# Atomizer_medical_V1_4.net
KiCad netlist of a schematic drawn in Altium Designer
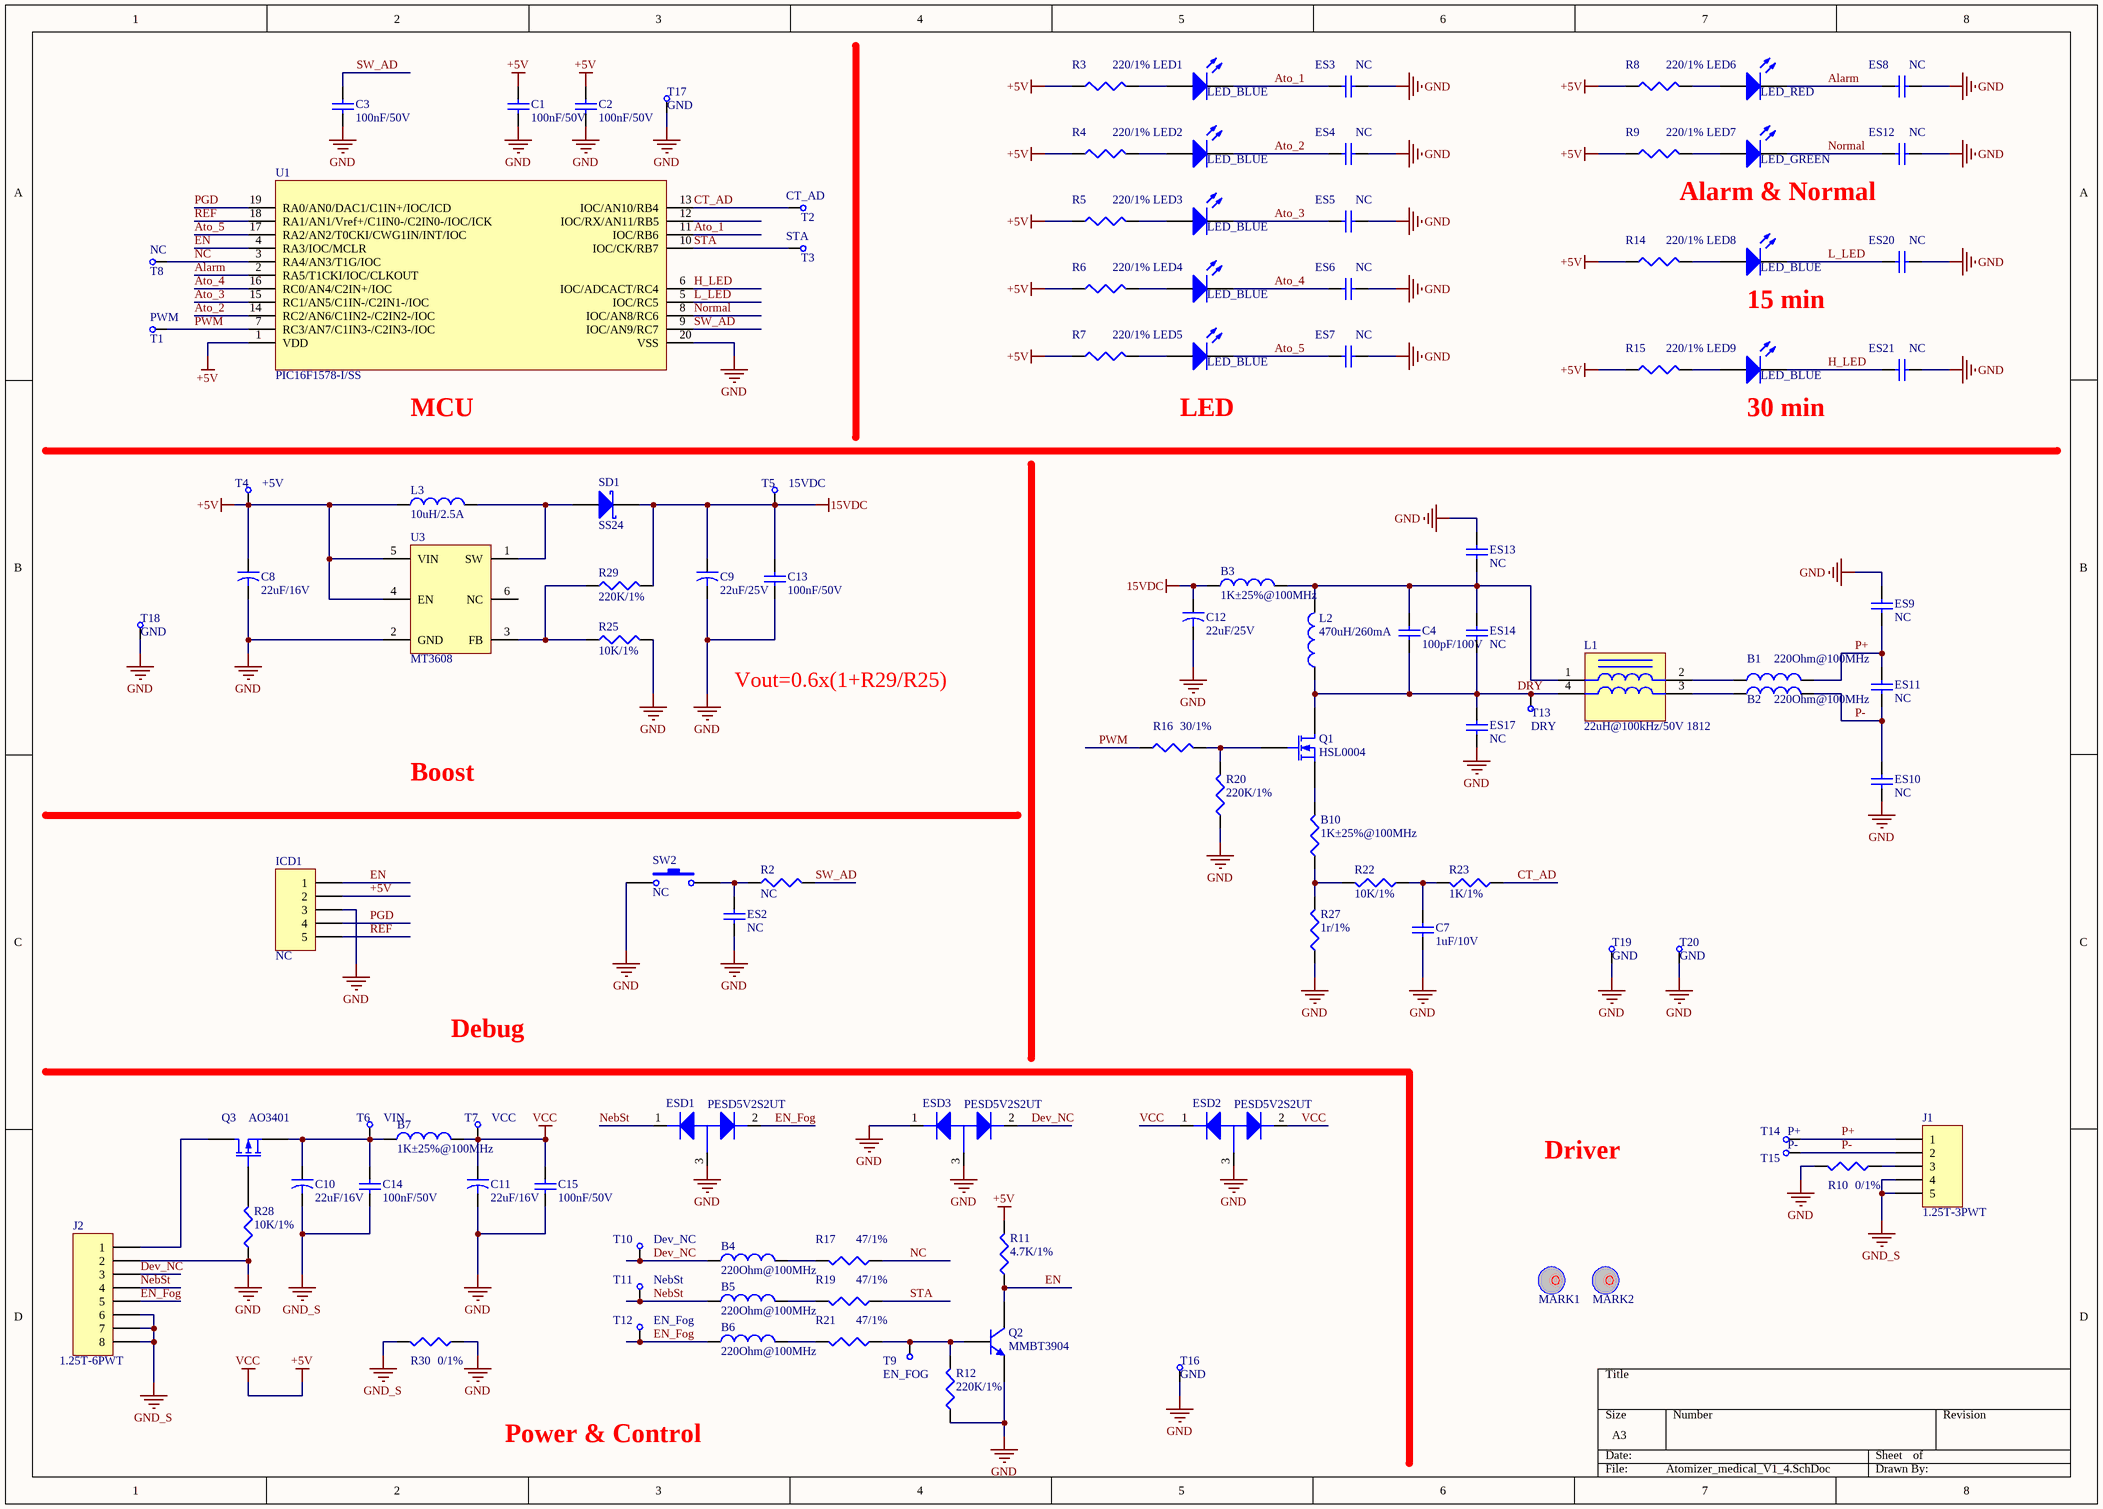
[diagram p0: Atomizer_medical_V1_4.SchDoc]

(export (version "E")
  (design (tool "Eeschema 10.0.6"))
  (components
    (comp (ref "B1")
      (value "220Ohm@100MHz")
      (footprint "0402-B")
      (description "Inductor")
      (fields (field (name "PUBLISHER") "Altium Limited"))
      (libsource (lib "Miscellaneous Devices") (part "Inductor"))
    )
    (comp (ref "B2")
      (value "220Ohm@100MHz")
      (footprint "0402-B")
      (description "Inductor")
      (fields (field (name "PUBLISHER") "Altium Limited"))
      (libsource (lib "Miscellaneous Devices") (part "Inductor"))
    )
    (comp (ref "B3")
      (value "1K±25%@100MHz")
      (footprint "0805-B")
      (description "Inductor")
      (fields (field (name "PUBLISHER") "Altium Limited"))
      (libsource (lib "Miscellaneous Devices") (part "Inductor"))
    )
    (comp (ref "B4")
      (value "220Ohm@100MHz")
      (footprint "0402-B")
      (description "Inductor")
      (fields (field (name "PUBLISHER") "Altium Limited"))
      (libsource (lib "Miscellaneous Devices") (part "Inductor"))
    )
    (comp (ref "B5")
      (value "220Ohm@100MHz")
      (footprint "0402-B")
      (description "Inductor")
      (fields (field (name "PUBLISHER") "Altium Limited"))
      (libsource (lib "Miscellaneous Devices") (part "Inductor"))
    )
    (comp (ref "B6")
      (value "220Ohm@100MHz")
      (footprint "0402-B")
      (description "Inductor")
      (fields (field (name "PUBLISHER") "Altium Limited"))
      (libsource (lib "Miscellaneous Devices") (part "Inductor"))
    )
    (comp (ref "B7")
      (value "1K±25%@100MHz")
      (footprint "0805-B")
      (description "Inductor")
      (fields (field (name "PUBLISHER") "Altium Limited"))
      (libsource (lib "Miscellaneous Devices") (part "Inductor"))
    )
    (comp (ref "B10")
      (value "1K±25%@100MHz")
      (footprint "0603")
      (description "Resistor")
      (fields (field (name "PUBLISHER") "Altium Limited"))
      (libsource (lib "Miscellaneous Devices") (part "Res3"))
    )
    (comp (ref "C1")
      (value "100nF/50V")
      (footprint "0402-C")
      (description "Capacitor (Semiconductor SIM Model)")
      (fields (field (name "PUBLISHER") "Altium Limited"))
      (libsource (lib "Miscellaneous Devices") (part "Cap Semi"))
    )
    (comp (ref "C2")
      (value "100nF/50V")
      (footprint "0402-C")
      (description "Capacitor (Semiconductor SIM Model)")
      (fields (field (name "PUBLISHER") "Altium Limited"))
      (libsource (lib "Miscellaneous Devices") (part "Cap Semi"))
    )
    (comp (ref "C3")
      (value "100nF/50V")
      (footprint "0402-C")
      (description "Capacitor (Semiconductor SIM Model)")
      (fields (field (name "PUBLISHER") "Altium Limited"))
      (libsource (lib "Miscellaneous Devices") (part "Cap Semi"))
    )
    (comp (ref "C4")
      (value "100pF/100V")
      (footprint "0805-C")
      (description "Capacitor (Semiconductor SIM Model)")
      (fields (field (name "PUBLISHER") "Altium Limited"))
      (libsource (lib "Miscellaneous Devices") (part "Cap Semi"))
    )
    (comp (ref "C7")
      (value "1uF/10V")
      (footprint "0402-C")
      (description "Capacitor (Semiconductor SIM Model)")
      (fields (field (name "PUBLISHER") "Altium Limited"))
      (libsource (lib "Miscellaneous Devices") (part "Cap Semi"))
    )
    (comp (ref "C8")
      (value "22uF/16V")
      (footprint "0805-C")
      (description "Capacitor")
      (fields (field (name "PUBLISHER") "Altium Limited"))
      (libsource (lib "Miscellaneous Devices") (part "Cap2"))
    )
    (comp (ref "C9")
      (value "22uF/25V")
      (footprint "1206-C")
      (description "Capacitor")
      (fields (field (name "PUBLISHER") "Altium Limited"))
      (libsource (lib "Miscellaneous Devices") (part "Cap2"))
    )
    (comp (ref "C10")
      (value "22uF/16V")
      (footprint "0805-C")
      (description "Capacitor")
      (fields (field (name "PUBLISHER") "Altium Limited"))
      (libsource (lib "Miscellaneous Devices") (part "Cap2"))
    )
    (comp (ref "C11")
      (value "22uF/16V")
      (footprint "0805-C")
      (description "Capacitor")
      (fields (field (name "PUBLISHER") "Altium Limited"))
      (libsource (lib "Miscellaneous Devices") (part "Cap2"))
    )
    (comp (ref "C12")
      (value "22uF/25V")
      (footprint "1206-C")
      (description "Capacitor")
      (fields (field (name "PUBLISHER") "Altium Limited"))
      (libsource (lib "Miscellaneous Devices") (part "Cap2"))
    )
    (comp (ref "C13")
      (value "100nF/50V")
      (footprint "0402-C")
      (description "Capacitor (Semiconductor SIM Model)")
      (fields (field (name "PUBLISHER") "Altium Limited"))
      (libsource (lib "Miscellaneous Devices") (part "Cap Semi"))
    )
    (comp (ref "C14")
      (value "100nF/50V")
      (footprint "0402-C")
      (description "Capacitor (Semiconductor SIM Model)")
      (fields (field (name "PUBLISHER") "Altium Limited"))
      (libsource (lib "Miscellaneous Devices") (part "Cap Semi"))
    )
    (comp (ref "C15")
      (value "100nF/50V")
      (footprint "0402-C")
      (description "Capacitor (Semiconductor SIM Model)")
      (fields (field (name "PUBLISHER") "Altium Limited"))
      (libsource (lib "Miscellaneous Devices") (part "Cap Semi"))
    )
    (comp (ref "ES2")
      (value "NC")
      (footprint "0402-C")
      (description "Capacitor (Semiconductor SIM Model)")
      (fields (field (name "PUBLISHER") "Altium Limited"))
      (libsource (lib "Miscellaneous Devices") (part "Cap Semi"))
    )
    (comp (ref "ES3")
      (value "NC")
      (footprint "0402-C")
      (description "Capacitor (Semiconductor SIM Model)")
      (fields (field (name "PUBLISHER") "Altium Limited"))
      (libsource (lib "Miscellaneous Devices") (part "Cap Semi"))
    )
    (comp (ref "ES4")
      (value "NC")
      (footprint "0402-C")
      (description "Capacitor (Semiconductor SIM Model)")
      (fields (field (name "PUBLISHER") "Altium Limited"))
      (libsource (lib "Miscellaneous Devices") (part "Cap Semi"))
    )
    (comp (ref "ES5")
      (value "NC")
      (footprint "0402-C")
      (description "Capacitor (Semiconductor SIM Model)")
      (fields (field (name "PUBLISHER") "Altium Limited"))
      (libsource (lib "Miscellaneous Devices") (part "Cap Semi"))
    )
    (comp (ref "ES6")
      (value "NC")
      (footprint "0402-C")
      (description "Capacitor (Semiconductor SIM Model)")
      (fields (field (name "PUBLISHER") "Altium Limited"))
      (libsource (lib "Miscellaneous Devices") (part "Cap Semi"))
    )
    (comp (ref "ES7")
      (value "NC")
      (footprint "0402-C")
      (description "Capacitor (Semiconductor SIM Model)")
      (fields (field (name "PUBLISHER") "Altium Limited"))
      (libsource (lib "Miscellaneous Devices") (part "Cap Semi"))
    )
    (comp (ref "ES8")
      (value "NC")
      (footprint "0402-C")
      (description "Capacitor (Semiconductor SIM Model)")
      (fields (field (name "PUBLISHER") "Altium Limited"))
      (libsource (lib "Miscellaneous Devices") (part "Cap Semi"))
    )
    (comp (ref "ES9")
      (value "NC")
      (footprint "0402-C")
      (description "Capacitor (Semiconductor SIM Model)")
      (fields (field (name "PUBLISHER") "Altium Limited"))
      (libsource (lib "Miscellaneous Devices") (part "Cap Semi"))
    )
    (comp (ref "ES10")
      (value "NC")
      (footprint "0402-C")
      (description "Capacitor (Semiconductor SIM Model)")
      (fields (field (name "PUBLISHER") "Altium Limited"))
      (libsource (lib "Miscellaneous Devices") (part "Cap Semi"))
    )
    (comp (ref "ES11")
      (value "NC")
      (footprint "0402-C")
      (description "Capacitor (Semiconductor SIM Model)")
      (fields (field (name "PUBLISHER") "Altium Limited"))
      (libsource (lib "Miscellaneous Devices") (part "Cap Semi"))
    )
    (comp (ref "ES12")
      (value "NC")
      (footprint "0402-C")
      (description "Capacitor (Semiconductor SIM Model)")
      (fields (field (name "PUBLISHER") "Altium Limited"))
      (libsource (lib "Miscellaneous Devices") (part "Cap Semi"))
    )
    (comp (ref "ES13")
      (value "NC")
      (footprint "0402-C")
      (description "Capacitor (Semiconductor SIM Model)")
      (fields (field (name "PUBLISHER") "Altium Limited"))
      (libsource (lib "Miscellaneous Devices") (part "Cap Semi"))
    )
    (comp (ref "ES14")
      (value "NC")
      (footprint "0402-C")
      (description "Capacitor (Semiconductor SIM Model)")
      (fields (field (name "PUBLISHER") "Altium Limited"))
      (libsource (lib "Miscellaneous Devices") (part "Cap Semi"))
    )
    (comp (ref "ES17")
      (value "NC")
      (footprint "0402-C")
      (description "Capacitor (Semiconductor SIM Model)")
      (fields (field (name "PUBLISHER") "Altium Limited"))
      (libsource (lib "Miscellaneous Devices") (part "Cap Semi"))
    )
    (comp (ref "ES20")
      (value "NC")
      (footprint "0402-C")
      (description "Capacitor (Semiconductor SIM Model)")
      (fields (field (name "PUBLISHER") "Altium Limited"))
      (libsource (lib "Miscellaneous Devices") (part "Cap Semi"))
    )
    (comp (ref "ES21")
      (value "NC")
      (footprint "0402-C")
      (description "Capacitor (Semiconductor SIM Model)")
      (fields (field (name "PUBLISHER") "Altium Limited"))
      (libsource (lib "Miscellaneous Devices") (part "Cap Semi"))
    )
    (comp (ref "ESD1")
      (value "PESD5V2S2UT")
      (footprint "SOT23")
      (description "ESD")
      (libsource (lib "Atomizer_medical") (part "ESD"))
    )
    (comp (ref "ESD2")
      (value "PESD5V2S2UT")
      (footprint "SOT23")
      (description "ESD")
      (libsource (lib "Atomizer_medical") (part "ESD"))
    )
    (comp (ref "ESD3")
      (value "PESD5V2S2UT")
      (footprint "SOT23")
      (description "ESD")
      (libsource (lib "Atomizer_medical") (part "ESD"))
    )
    (comp (ref "ICD1")
      (value "NC")
      (footprint "SIP1X5P1.25A-180-DIP")
      (description "Header, 5-Pin")
      (fields (field (name "PUBLISHER") "Altium Limited"))
      (libsource (lib "") (part "Header 5_1"))
    )
    (comp (ref "J1")
      (value "1.25T-3PWT")
      (footprint "WAFER_1.25MMX3P_180")
      (description "Header, 5-Pin")
      (fields (field (name "PUBLISHER") "Altium Limited"))
      (libsource (lib "Miscellaneous Connectors") (part "Header 5"))
    )
    (comp (ref "J2")
      (value "1.25T-6PWT")
      (footprint "WAFER_1.25MMX6P_180")
      (description "Header, 8-Pin")
      (fields (field (name "PUBLISHER") "Altium Limited"))
      (libsource (lib "Miscellaneous Connectors") (part "Header 8"))
    )
    (comp (ref "L1")
      (value "22uH@100kHz/50V 1812")
      (footprint "LINEFILTER")
      (description "Inductor_common")
      (libsource (lib "Atomizer_medical") (part "Inductor_common"))
    )
    (comp (ref "L2")
      (value "470uH/260mA")
      (footprint "SP0502")
      (description "Inductor")
      (fields (field (name "PUBLISHER") "Altium Limited"))
      (libsource (lib "Miscellaneous Devices") (part "Inductor"))
    )
    (comp (ref "L3")
      (value "10uH/2.5A")
      (footprint "SP0502")
      (description "Inductor")
      (fields (field (name "PUBLISHER") "Altium Limited"))
      (libsource (lib "Miscellaneous Devices") (part "Inductor"))
    )
    (comp (ref "LED1")
      (value "LED_BLUE")
      (footprint "LED0603")
      (description "Typical RED, GREEN, YELLOW, AMBER GaAs LED")
      (fields (field (name "PUBLISHER") "Altium Limited"))
      (libsource (lib "Miscellaneous Devices") (part "LED2"))
    )
    (comp (ref "LED2")
      (value "LED_BLUE")
      (footprint "LED0603")
      (description "Typical RED, GREEN, YELLOW, AMBER GaAs LED")
      (fields (field (name "PUBLISHER") "Altium Limited"))
      (libsource (lib "Miscellaneous Devices") (part "LED2"))
    )
    (comp (ref "LED3")
      (value "LED_BLUE")
      (footprint "LED0603")
      (description "Typical RED, GREEN, YELLOW, AMBER GaAs LED")
      (fields (field (name "PUBLISHER") "Altium Limited"))
      (libsource (lib "Miscellaneous Devices") (part "LED2"))
    )
    (comp (ref "LED4")
      (value "LED_BLUE")
      (footprint "LED0603")
      (description "Typical RED, GREEN, YELLOW, AMBER GaAs LED")
      (fields (field (name "PUBLISHER") "Altium Limited"))
      (libsource (lib "Miscellaneous Devices") (part "LED2"))
    )
    (comp (ref "LED5")
      (value "LED_BLUE")
      (footprint "LED0603")
      (description "Typical RED, GREEN, YELLOW, AMBER GaAs LED")
      (fields (field (name "PUBLISHER") "Altium Limited"))
      (libsource (lib "Miscellaneous Devices") (part "LED2"))
    )
    (comp (ref "LED6")
      (value "LED_RED")
      (footprint "LED0603")
      (description "Typical RED, GREEN, YELLOW, AMBER GaAs LED")
      (fields (field (name "PUBLISHER") "Altium Limited"))
      (libsource (lib "Miscellaneous Devices") (part "LED2"))
    )
    (comp (ref "LED7")
      (value "LED_GREEN")
      (footprint "LED0603")
      (description "Typical RED, GREEN, YELLOW, AMBER GaAs LED")
      (fields (field (name "PUBLISHER") "Altium Limited"))
      (libsource (lib "Miscellaneous Devices") (part "LED2"))
    )
    (comp (ref "LED8")
      (value "LED_BLUE")
      (footprint "LED0603")
      (description "Typical RED, GREEN, YELLOW, AMBER GaAs LED")
      (fields (field (name "PUBLISHER") "Altium Limited"))
      (libsource (lib "Miscellaneous Devices") (part "LED2"))
    )
    (comp (ref "LED9")
      (value "LED_BLUE")
      (footprint "LED0603")
      (description "Typical RED, GREEN, YELLOW, AMBER GaAs LED")
      (fields (field (name "PUBLISHER") "Altium Limited"))
      (libsource (lib "Miscellaneous Devices") (part "LED2"))
    )
    (comp (ref "MARK1")
      (value "MARK_POINT")
      (footprint "MARK_POINT")
      (libsource (lib "others") (part "MARK_POINT"))
    )
    (comp (ref "MARK2")
      (value "MARK_POINT")
      (footprint "MARK_POINT")
      (libsource (lib "others") (part "MARK_POINT"))
    )
    (comp (ref "Q1")
      (value "HSL0004")
      (footprint "SOT223")
      (description "N-Channel MOSFET")
      (fields (field (name "PUBLISHER") "Altium Limited"))
      (libsource (lib "Miscellaneous Devices") (part "MOSFET-N"))
    )
    (comp (ref "Q2")
      (value "MMBT3904")
      (footprint "SOT23")
      (description "NPN Bipolar Transistor")
      (fields (field (name "PUBLISHER") "Altium Limited"))
      (libsource (lib "Miscellaneous Devices") (part "NPN"))
    )
    (comp (ref "Q3")
      (value "AO3401")
      (footprint "SOT23")
      (description "P-Channel MOSFET")
      (fields (field (name "PUBLISHER") "Altium Limited"))
      (libsource (lib "Miscellaneous Devices") (part "MOSFET-P"))
    )
    (comp (ref "R2")
      (value "NC")
      (footprint "0402")
      (description "Resistor")
      (fields (field (name "PUBLISHER") "Altium Limited"))
      (libsource (lib "Miscellaneous Devices") (part "Res3"))
    )
    (comp (ref "R3")
      (value "220/1%")
      (footprint "0402")
      (description "Resistor")
      (fields (field (name "PUBLISHER") "Altium Limited"))
      (libsource (lib "Miscellaneous Devices") (part "Res3"))
    )
    (comp (ref "R4")
      (value "220/1%")
      (footprint "0402")
      (description "Resistor")
      (fields (field (name "PUBLISHER") "Altium Limited"))
      (libsource (lib "Miscellaneous Devices") (part "Res3"))
    )
    (comp (ref "R5")
      (value "220/1%")
      (footprint "0402")
      (description "Resistor")
      (fields (field (name "PUBLISHER") "Altium Limited"))
      (libsource (lib "Miscellaneous Devices") (part "Res3"))
    )
    (comp (ref "R6")
      (value "220/1%")
      (footprint "0402")
      (description "Resistor")
      (fields (field (name "PUBLISHER") "Altium Limited"))
      (libsource (lib "Miscellaneous Devices") (part "Res3"))
    )
    (comp (ref "R7")
      (value "220/1%")
      (footprint "0402")
      (description "Resistor")
      (fields (field (name "PUBLISHER") "Altium Limited"))
      (libsource (lib "Miscellaneous Devices") (part "Res3"))
    )
    (comp (ref "R8")
      (value "220/1%")
      (footprint "0402")
      (description "Resistor")
      (fields (field (name "PUBLISHER") "Altium Limited"))
      (libsource (lib "Miscellaneous Devices") (part "Res3"))
    )
    (comp (ref "R9")
      (value "220/1%")
      (footprint "0402")
      (description "Resistor")
      (fields (field (name "PUBLISHER") "Altium Limited"))
      (libsource (lib "Miscellaneous Devices") (part "Res3"))
    )
    (comp (ref "R10")
      (value "0/1%")
      (footprint "0603")
      (description "Resistor")
      (fields (field (name "PUBLISHER") "Altium Limited"))
      (libsource (lib "Miscellaneous Devices") (part "Res3"))
    )
    (comp (ref "R11")
      (value "4.7K/1%")
      (footprint "0402")
      (description "Resistor")
      (fields (field (name "PUBLISHER") "Altium Limited"))
      (libsource (lib "Miscellaneous Devices") (part "Res3"))
    )
    (comp (ref "R12")
      (value "220K/1%")
      (footprint "0402")
      (description "Resistor")
      (fields (field (name "PUBLISHER") "Altium Limited"))
      (libsource (lib "Miscellaneous Devices") (part "Res3"))
    )
    (comp (ref "R14")
      (value "220/1%")
      (footprint "0402")
      (description "Resistor")
      (fields (field (name "PUBLISHER") "Altium Limited"))
      (libsource (lib "Miscellaneous Devices") (part "Res3"))
    )
    (comp (ref "R15")
      (value "220/1%")
      (footprint "0402")
      (description "Resistor")
      (fields (field (name "PUBLISHER") "Altium Limited"))
      (libsource (lib "Miscellaneous Devices") (part "Res3"))
    )
    (comp (ref "R16")
      (value "30/1%")
      (footprint "0402")
      (description "Resistor")
      (fields (field (name "PUBLISHER") "Altium Limited"))
      (libsource (lib "Miscellaneous Devices") (part "Res3"))
    )
    (comp (ref "R17")
      (value "47/1%")
      (footprint "0402")
      (description "Resistor")
      (fields (field (name "PUBLISHER") "Altium Limited"))
      (libsource (lib "Miscellaneous Devices") (part "Res3"))
    )
    (comp (ref "R19")
      (value "47/1%")
      (footprint "0402")
      (description "Resistor")
      (fields (field (name "PUBLISHER") "Altium Limited"))
      (libsource (lib "Miscellaneous Devices") (part "Res3"))
    )
    (comp (ref "R20")
      (value "220K/1%")
      (footprint "0402")
      (description "Resistor")
      (fields (field (name "PUBLISHER") "Altium Limited"))
      (libsource (lib "Miscellaneous Devices") (part "Res3"))
    )
    (comp (ref "R21")
      (value "47/1%")
      (footprint "0402")
      (description "Resistor")
      (fields (field (name "PUBLISHER") "Altium Limited"))
      (libsource (lib "Miscellaneous Devices") (part "Res3"))
    )
    (comp (ref "R22")
      (value "10K/1%")
      (footprint "0402")
      (description "Resistor")
      (fields (field (name "PUBLISHER") "Altium Limited"))
      (libsource (lib "Miscellaneous Devices") (part "Res3"))
    )
    (comp (ref "R23")
      (value "1K/1%")
      (footprint "0402")
      (description "Resistor")
      (fields (field (name "PUBLISHER") "Altium Limited"))
      (libsource (lib "Miscellaneous Devices") (part "Res3"))
    )
    (comp (ref "R25")
      (value "10K/1%")
      (footprint "0402")
      (description "Resistor")
      (fields (field (name "PUBLISHER") "Altium Limited"))
      (libsource (lib "Miscellaneous Devices") (part "Res3"))
    )
    (comp (ref "R27")
      (value "1r/1%")
      (footprint "0805")
      (description "Resistor")
      (fields (field (name "PUBLISHER") "Altium Limited"))
      (libsource (lib "Miscellaneous Devices") (part "Res3"))
    )
    (comp (ref "R28")
      (value "10K/1%")
      (footprint "0402")
      (description "Resistor")
      (fields (field (name "PUBLISHER") "Altium Limited"))
      (libsource (lib "Miscellaneous Devices") (part "Res3"))
    )
    (comp (ref "R29")
      (value "220K/1%")
      (footprint "0402")
      (description "Resistor")
      (fields (field (name "PUBLISHER") "Altium Limited"))
      (libsource (lib "Miscellaneous Devices") (part "Res3"))
    )
    (comp (ref "R30")
      (value "0/1%")
      (footprint "0603")
      (description "Resistor")
      (fields (field (name "PUBLISHER") "Altium Limited"))
      (libsource (lib "Miscellaneous Devices") (part "Res3"))
    )
    (comp (ref "SD1")
      (value "SS24")
      (footprint "SMA-403D")
      (description "Schottky Diode")
      (fields (field (name "PUBLISHER") "Altium Limited"))
      (libsource (lib "Miscellaneous Devices") (part "D Schottky"))
    )
    (comp (ref "SW2")
      (value "NC")
      (footprint "HTS-52MB")
      (description "Switch")
      (fields (field (name "PUBLISHER") "Altium Limited"))
      (libsource (lib "Miscellaneous Devices") (part "SW-PB"))
    )
    (comp (ref "T1")
      (value "PWM")
      (footprint "TP-SIP-1-Small1")
      (libsource (lib "others") (part "TP-SIP-1-Small"))
    )
    (comp (ref "T2")
      (value "CT_AD")
      (footprint "TP-SIP-1-Small1")
      (libsource (lib "others") (part "TP-SIP-1-Small"))
    )
    (comp (ref "T3")
      (value "STA")
      (footprint "TP-SIP-1-Small1")
      (libsource (lib "others") (part "TP-SIP-1-Small"))
    )
    (comp (ref "T4")
      (value "+5V")
      (footprint "TP-SIP-1-Small1")
      (libsource (lib "others") (part "TP-SIP-1-Small"))
    )
    (comp (ref "T5")
      (value "15VDC")
      (footprint "TP-SIP-1-Small1")
      (libsource (lib "others") (part "TP-SIP-1-Small"))
    )
    (comp (ref "T6")
      (value "VIN")
      (footprint "TP-SIP-1-Small1")
      (libsource (lib "others") (part "TP-SIP-1-Small"))
    )
    (comp (ref "T7")
      (value "VCC")
      (footprint "TP-SIP-1-Small1")
      (libsource (lib "others") (part "TP-SIP-1-Small"))
    )
    (comp (ref "T8")
      (value "NC")
      (footprint "TP-SIP-1-Small1")
      (libsource (lib "others") (part "TP-SIP-1-Small"))
    )
    (comp (ref "T9")
      (value "EN_FOG")
      (footprint "TP-SIP-1-Small1")
      (libsource (lib "others") (part "TP-SIP-1-Small"))
    )
    (comp (ref "T10")
      (value "Dev_NC")
      (footprint "TP-SIP-1-Small1")
      (libsource (lib "others") (part "TP-SIP-1-Small"))
    )
    (comp (ref "T11")
      (value "NebSt")
      (footprint "TP-SIP-1-Small1")
      (libsource (lib "others") (part "TP-SIP-1-Small"))
    )
    (comp (ref "T12")
      (value "EN_Fog")
      (footprint "TP-SIP-1-Small1")
      (libsource (lib "others") (part "TP-SIP-1-Small"))
    )
    (comp (ref "T13")
      (value "DRY")
      (footprint "TP-SIP-1-Small1")
      (libsource (lib "others") (part "TP-SIP-1-Small"))
    )
    (comp (ref "T14")
      (value "P+")
      (footprint "TP-SIP-1-Small1")
      (libsource (lib "others") (part "TP-SIP-1-Small"))
    )
    (comp (ref "T15")
      (value "P-")
      (footprint "TP-SIP-1-Small1")
      (libsource (lib "others") (part "TP-SIP-1-Small"))
    )
    (comp (ref "T16")
      (value "GND")
      (footprint "TP-SIP-1-Small1")
      (libsource (lib "others") (part "TP-SIP-1-Small"))
    )
    (comp (ref "T17")
      (value "GND")
      (footprint "TP-SIP-1-Small1")
      (libsource (lib "others") (part "TP-SIP-1-Small"))
    )
    (comp (ref "T18")
      (value "GND")
      (footprint "TP-SIP-1-Small1")
      (libsource (lib "others") (part "TP-SIP-1-Small"))
    )
    (comp (ref "T19")
      (value "GND")
      (footprint "TP-SIP-1-Small1")
      (libsource (lib "others") (part "TP-SIP-1-Small"))
    )
    (comp (ref "T20")
      (value "GND")
      (footprint "TP-SIP-1-Small1")
      (libsource (lib "others") (part "TP-SIP-1-Small"))
    )
    (comp (ref "U1")
      (value "PIC16F1578-I/SS")
      (footprint "SSOP-20")
      (description "PIC16  SSOP-20")
      (libsource (lib "Atomizer_medical") (part "PIC16F1578-I/SS"))
    )
    (comp (ref "U3")
      (value "MT3608")
      (footprint "SOT95P280X110-6N")
      (description "DC-DC-BOOST")
      (libsource (lib "Atomizer_medical") (part "MT3608"))
    )
  )
  (nets
    (net (code "1") (name "+5V") (class "Default")
      (node (ref "B7") (pin "2") (pinfunction "2_2") (pintype "passive"))
      (node (ref "C1") (pin "2") (pinfunction "2_2") (pintype "passive"))
      (node (ref "C11") (pin "1") (pinfunction "1_1") (pintype "passive"))
      (node (ref "C15") (pin "1") (pinfunction "1_1") (pintype "passive"))
      (node (ref "C2") (pin "2") (pinfunction "2_2") (pintype "passive"))
      (node (ref "C8") (pin "1") (pinfunction "1_1") (pintype "passive"))
      (node (ref "ESD2") (pin "1") (pinfunction "S_1") (pintype "passive"))
      (node (ref "ESD2") (pin "2") (pinfunction "S_2") (pintype "passive"))
      (node (ref "ICD1") (pin "2") (pinfunction "2_2") (pintype "passive"))
      (node (ref "L3") (pin "1") (pinfunction "1_1") (pintype "passive"))
      (node (ref "R11") (pin "2") (pinfunction "2_2") (pintype "passive"))
      (node (ref "R14") (pin "1") (pinfunction "1_1") (pintype "passive"))
      (node (ref "R15") (pin "1") (pinfunction "1_1") (pintype "passive"))
      (node (ref "R3") (pin "1") (pinfunction "1_1") (pintype "passive"))
      (node (ref "R4") (pin "1") (pinfunction "1_1") (pintype "passive"))
      (node (ref "R5") (pin "1") (pinfunction "1_1") (pintype "passive"))
      (node (ref "R6") (pin "1") (pinfunction "1_1") (pintype "passive"))
      (node (ref "R7") (pin "1") (pinfunction "1_1") (pintype "passive"))
      (node (ref "R8") (pin "1") (pinfunction "1_1") (pintype "passive"))
      (node (ref "R9") (pin "1") (pinfunction "1_1") (pintype "passive"))
      (node (ref "T4") (pin "1") (pinfunction "1_1") (pintype "passive"))
      (node (ref "T7") (pin "1") (pinfunction "1_1") (pintype "passive"))
      (node (ref "U1") (pin "1") (pinfunction "VDD_1") (pintype "passive"))
      (node (ref "U3") (pin "4") (pinfunction "EN_4") (pintype "passive"))
      (node (ref "U3") (pin "5") (pinfunction "VIN_5") (pintype "passive"))
    )
    (net (code "2") (name "/Alarm") (class "Default")
      (node (ref "ES8") (pin "2") (pinfunction "2_2") (pintype "passive"))
      (node (ref "LED6") (pin "2") (pinfunction "K_2") (pintype "passive"))
      (node (ref "U1") (pin "2") (pinfunction "RA5/T1CKI/IOC/CLKOUT_2") (pintype "passive"))
    )
    (net (code "3") (name "/Ato_1") (class "Default")
      (node (ref "ES3") (pin "2") (pinfunction "2_2") (pintype "passive"))
      (node (ref "LED1") (pin "2") (pinfunction "K_2") (pintype "passive"))
      (node (ref "U1") (pin "11") (pinfunction "IOC/RB6_11") (pintype "passive"))
    )
    (net (code "4") (name "/Ato_2") (class "Default")
      (node (ref "ES4") (pin "2") (pinfunction "2_2") (pintype "passive"))
      (node (ref "LED2") (pin "2") (pinfunction "K_2") (pintype "passive"))
      (node (ref "U1") (pin "14") (pinfunction "RC2/AN6/C1IN2-/C2IN2-/IOC_14") (pintype "passive"))
    )
    (net (code "5") (name "/Ato_3") (class "Default")
      (node (ref "ES5") (pin "2") (pinfunction "2_2") (pintype "passive"))
      (node (ref "LED3") (pin "2") (pinfunction "K_2") (pintype "passive"))
      (node (ref "U1") (pin "15") (pinfunction "RC1/AN5/C1IN-/C2IN1-/IOC_15") (pintype "passive"))
    )
    (net (code "6") (name "/Ato_4") (class "Default")
      (node (ref "ES6") (pin "2") (pinfunction "2_2") (pintype "passive"))
      (node (ref "LED4") (pin "2") (pinfunction "K_2") (pintype "passive"))
      (node (ref "U1") (pin "16") (pinfunction "RC0/AN4/C2IN+/IOC_16") (pintype "passive"))
    )
    (net (code "7") (name "/Ato_5") (class "Default")
      (node (ref "ES7") (pin "2") (pinfunction "2_2") (pintype "passive"))
      (node (ref "LED5") (pin "2") (pinfunction "K_2") (pintype "passive"))
      (node (ref "U1") (pin "17") (pinfunction "RA2/AN2/T0CKI/CWG1IN/INT/IOC_17") (pintype "passive"))
    )
    (net (code "8") (name "/CT_AD") (class "Default")
      (node (ref "R23") (pin "1") (pinfunction "1_1") (pintype "passive"))
      (node (ref "T2") (pin "1") (pinfunction "1_1") (pintype "passive"))
      (node (ref "U1") (pin "13") (pinfunction "IOC/AN10/RB4_13") (pintype "passive"))
    )
    (net (code "9") (name "/DRY") (class "Default")
      (node (ref "C4") (pin "2") (pinfunction "2_2") (pintype "passive"))
      (node (ref "ES14") (pin "2") (pinfunction "2_2") (pintype "passive"))
      (node (ref "ES17") (pin "1") (pinfunction "1_1") (pintype "passive"))
      (node (ref "L1") (pin "4") (pinfunction "4_4") (pintype "passive"))
      (node (ref "L2") (pin "1") (pinfunction "1_1") (pintype "passive"))
      (node (ref "Q1") (pin "2") (pinfunction "D_2") (pintype "passive"))
      (node (ref "T13") (pin "1") (pinfunction "1_1") (pintype "passive"))
    )
    (net (code "10") (name "/Dev_NC") (class "Default")
      (node (ref "B4") (pin "1") (pinfunction "1_1") (pintype "passive"))
      (node (ref "ESD3") (pin "2") (pinfunction "S_2") (pintype "passive"))
      (node (ref "J2") (pin "3") (pinfunction "3_3") (pintype "passive"))
      (node (ref "T10") (pin "1") (pinfunction "1_1") (pintype "passive"))
    )
    (net (code "11") (name "/EN") (class "Default")
      (node (ref "ICD1") (pin "1") (pinfunction "1_1") (pintype "passive"))
      (node (ref "Q2") (pin "3") (pinfunction "C_3") (pintype "passive"))
      (node (ref "R11") (pin "1") (pinfunction "1_1") (pintype "passive"))
      (node (ref "U1") (pin "4") (pinfunction "RA3/IOC/MCLR_4") (pintype "passive"))
    )
    (net (code "12") (name "/EN_Fog") (class "Default")
      (node (ref "B6") (pin "1") (pinfunction "1_1") (pintype "passive"))
      (node (ref "ESD1") (pin "2") (pinfunction "S_2") (pintype "passive"))
      (node (ref "J2") (pin "5") (pinfunction "5_5") (pintype "passive"))
      (node (ref "T12") (pin "1") (pinfunction "1_1") (pintype "passive"))
    )
    (net (code "13") (name "/H_LED") (class "Default")
      (node (ref "ES21") (pin "2") (pinfunction "2_2") (pintype "passive"))
      (node (ref "LED9") (pin "2") (pinfunction "K_2") (pintype "passive"))
      (node (ref "U1") (pin "6") (pinfunction "IOC/ADCACT/RC4_6") (pintype "passive"))
    )
    (net (code "14") (name "/L_LED") (class "Default")
      (node (ref "ES20") (pin "2") (pinfunction "2_2") (pintype "passive"))
      (node (ref "LED8") (pin "2") (pinfunction "K_2") (pintype "passive"))
      (node (ref "U1") (pin "5") (pinfunction "IOC/RC5_5") (pintype "passive"))
    )
    (net (code "15") (name "/NC") (class "Default")
      (node (ref "R17") (pin "1") (pinfunction "1_1") (pintype "passive"))
      (node (ref "T8") (pin "1") (pinfunction "1_1") (pintype "passive"))
      (node (ref "U1") (pin "3") (pinfunction "RA4/AN3/T1G/IOC_3") (pintype "passive"))
    )
    (net (code "16") (name "/NebSt") (class "Default")
      (node (ref "B5") (pin "1") (pinfunction "1_1") (pintype "passive"))
      (node (ref "ESD1") (pin "1") (pinfunction "S_1") (pintype "passive"))
      (node (ref "J2") (pin "4") (pinfunction "4_4") (pintype "passive"))
      (node (ref "T11") (pin "1") (pinfunction "1_1") (pintype "passive"))
    )
    (net (code "17") (name "/Normal") (class "Default")
      (node (ref "ES12") (pin "2") (pinfunction "2_2") (pintype "passive"))
      (node (ref "LED7") (pin "2") (pinfunction "K_2") (pintype "passive"))
      (node (ref "U1") (pin "8") (pinfunction "IOC/AN8/RC6_8") (pintype "passive"))
    )
    (net (code "18") (name "/P+") (class "Default")
      (node (ref "B1") (pin "2") (pinfunction "2_2") (pintype "passive"))
      (node (ref "ES11") (pin "1") (pinfunction "1_1") (pintype "passive"))
      (node (ref "ES9") (pin "2") (pinfunction "2_2") (pintype "passive"))
      (node (ref "J1") (pin "1") (pinfunction "1_1") (pintype "passive"))
      (node (ref "T14") (pin "1") (pinfunction "1_1") (pintype "passive"))
    )
    (net (code "19") (name "/P-") (class "Default")
      (node (ref "B2") (pin "2") (pinfunction "2_2") (pintype "passive"))
      (node (ref "ES10") (pin "1") (pinfunction "1_1") (pintype "passive"))
      (node (ref "ES11") (pin "2") (pinfunction "2_2") (pintype "passive"))
      (node (ref "J1") (pin "2") (pinfunction "2_2") (pintype "passive"))
      (node (ref "T15") (pin "1") (pinfunction "1_1") (pintype "passive"))
    )
    (net (code "20") (name "/PGD") (class "Default")
      (node (ref "ICD1") (pin "4") (pinfunction "4_4") (pintype "passive"))
      (node (ref "U1") (pin "19") (pinfunction "RA0/AN0/DAC1/C1IN+/IOC/ICD_19") (pintype "passive"))
    )
    (net (code "21") (name "/PWM") (class "Default")
      (node (ref "R16") (pin "1") (pinfunction "1_1") (pintype "passive"))
      (node (ref "T1") (pin "1") (pinfunction "1_1") (pintype "passive"))
      (node (ref "U1") (pin "7") (pinfunction "RC3/AN7/C1IN3-/C2IN3-/IOC_7") (pintype "passive"))
    )
    (net (code "22") (name "/REF") (class "Default")
      (node (ref "ICD1") (pin "5") (pinfunction "5_5") (pintype "passive"))
      (node (ref "U1") (pin "18") (pinfunction "RA1/AN1/Vref+/C1IN0-/C2IN0-/IOC/ICK_18") (pintype "passive"))
    )
    (net (code "23") (name "/STA") (class "Default")
      (node (ref "R19") (pin "1") (pinfunction "1_1") (pintype "passive"))
      (node (ref "T3") (pin "1") (pinfunction "1_1") (pintype "passive"))
      (node (ref "U1") (pin "10") (pinfunction "IOC/CK/RB7_10") (pintype "passive"))
    )
    (net (code "24") (name "/SW_AD") (class "Default")
      (node (ref "C3") (pin "2") (pinfunction "2_2") (pintype "passive"))
      (node (ref "R2") (pin "2") (pinfunction "2_2") (pintype "passive"))
      (node (ref "U1") (pin "9") (pinfunction "IOC/AN9/RC7_9") (pintype "passive"))
    )
    (net (code "25") (name "15VDC") (class "Default")
      (node (ref "B3") (pin "1") (pinfunction "1_1") (pintype "passive"))
      (node (ref "C12") (pin "1") (pinfunction "1_1") (pintype "passive"))
      (node (ref "C13") (pin "1") (pinfunction "1_1") (pintype "passive"))
      (node (ref "C9") (pin "1") (pinfunction "1_1") (pintype "passive"))
      (node (ref "R29") (pin "2") (pinfunction "2_2") (pintype "passive"))
      (node (ref "SD1") (pin "2") (pinfunction "K_2") (pintype "passive"))
      (node (ref "T5") (pin "1") (pinfunction "1_1") (pintype "passive"))
    )
    (net (code "26") (name "GND") (class "Default")
      (node (ref "C1") (pin "1") (pinfunction "1_1") (pintype "passive"))
      (node (ref "C11") (pin "2") (pinfunction "2_2") (pintype "passive"))
      (node (ref "C12") (pin "2") (pinfunction "2_2") (pintype "passive"))
      (node (ref "C13") (pin "2") (pinfunction "2_2") (pintype "passive"))
      (node (ref "C15") (pin "2") (pinfunction "2_2") (pintype "passive"))
      (node (ref "C2") (pin "1") (pinfunction "1_1") (pintype "passive"))
      (node (ref "C3") (pin "1") (pinfunction "1_1") (pintype "passive"))
      (node (ref "C7") (pin "2") (pinfunction "2_2") (pintype "passive"))
      (node (ref "C8") (pin "2") (pinfunction "2_2") (pintype "passive"))
      (node (ref "C9") (pin "2") (pinfunction "2_2") (pintype "passive"))
      (node (ref "ES10") (pin "2") (pinfunction "2_2") (pintype "passive"))
      (node (ref "ES12") (pin "1") (pinfunction "1_1") (pintype "passive"))
      (node (ref "ES13") (pin "1") (pinfunction "1_1") (pintype "passive"))
      (node (ref "ES17") (pin "2") (pinfunction "2_2") (pintype "passive"))
      (node (ref "ES2") (pin "2") (pinfunction "2_2") (pintype "passive"))
      (node (ref "ES20") (pin "1") (pinfunction "1_1") (pintype "passive"))
      (node (ref "ES21") (pin "1") (pinfunction "1_1") (pintype "passive"))
      (node (ref "ES3") (pin "1") (pinfunction "1_1") (pintype "passive"))
      (node (ref "ES4") (pin "1") (pinfunction "1_1") (pintype "passive"))
      (node (ref "ES5") (pin "1") (pinfunction "1_1") (pintype "passive"))
      (node (ref "ES6") (pin "1") (pinfunction "1_1") (pintype "passive"))
      (node (ref "ES7") (pin "1") (pinfunction "1_1") (pintype "passive"))
      (node (ref "ES8") (pin "1") (pinfunction "1_1") (pintype "passive"))
      (node (ref "ES9") (pin "1") (pinfunction "1_1") (pintype "passive"))
      (node (ref "ESD1") (pin "3") (pinfunction "G_3") (pintype "passive"))
      (node (ref "ESD2") (pin "3") (pinfunction "G_3") (pintype "passive"))
      (node (ref "ESD3") (pin "1") (pinfunction "S_1") (pintype "passive"))
      (node (ref "ESD3") (pin "3") (pinfunction "G_3") (pintype "passive"))
      (node (ref "ICD1") (pin "3") (pinfunction "3_3") (pintype "passive"))
      (node (ref "J2") (pin "2") (pinfunction "2_2") (pintype "passive"))
      (node (ref "Q2") (pin "2") (pinfunction "E_2") (pintype "passive"))
      (node (ref "R10") (pin "2") (pinfunction "2_2") (pintype "passive"))
      (node (ref "R12") (pin "1") (pinfunction "1_1") (pintype "passive"))
      (node (ref "R20") (pin "1") (pinfunction "1_1") (pintype "passive"))
      (node (ref "R25") (pin "2") (pinfunction "2_2") (pintype "passive"))
      (node (ref "R27") (pin "1") (pinfunction "1_1") (pintype "passive"))
      (node (ref "R28") (pin "1") (pinfunction "1_1") (pintype "passive"))
      (node (ref "R30") (pin "1") (pinfunction "1_1") (pintype "passive"))
      (node (ref "SW2") (pin "1") (pinfunction "1_1") (pintype "passive"))
      (node (ref "T16") (pin "1") (pinfunction "1_1") (pintype "passive"))
      (node (ref "T17") (pin "1") (pinfunction "1_1") (pintype "passive"))
      (node (ref "T18") (pin "1") (pinfunction "1_1") (pintype "passive"))
      (node (ref "T19") (pin "1") (pinfunction "1_1") (pintype "passive"))
      (node (ref "T20") (pin "1") (pinfunction "1_1") (pintype "passive"))
      (node (ref "U1") (pin "20") (pinfunction "VSS_20") (pintype "passive"))
      (node (ref "U3") (pin "2") (pinfunction "GND_2") (pintype "passive"))
    )
    (net (code "27") (name "GND_S") (class "Default")
      (node (ref "C10") (pin "2") (pinfunction "2_2") (pintype "passive"))
      (node (ref "C14") (pin "2") (pinfunction "2_2") (pintype "passive"))
      (node (ref "J1") (pin "4") (pinfunction "4_4") (pintype "passive"))
      (node (ref "J1") (pin "5") (pinfunction "5_5") (pintype "passive"))
      (node (ref "J2") (pin "6") (pinfunction "6_6") (pintype "passive"))
      (node (ref "J2") (pin "7") (pinfunction "7_7") (pintype "passive"))
      (node (ref "J2") (pin "8") (pinfunction "8_8") (pintype "passive"))
      (node (ref "R30") (pin "2") (pinfunction "2_2") (pintype "passive"))
    )
    (net (code "28") (name "Net-(B1-Pad1)") (class "Default")
      (node (ref "B1") (pin "1") (pinfunction "1_1") (pintype "passive"))
      (node (ref "L1") (pin "2") (pinfunction "2_2") (pintype "passive"))
    )
    (net (code "29") (name "Net-(B2-Pad1)") (class "Default")
      (node (ref "B2") (pin "1") (pinfunction "1_1") (pintype "passive"))
      (node (ref "L1") (pin "3") (pinfunction "3_3") (pintype "passive"))
    )
    (net (code "30") (name "Net-(B3-Pad2)") (class "Default")
      (node (ref "B3") (pin "2") (pinfunction "2_2") (pintype "passive"))
      (node (ref "C4") (pin "1") (pinfunction "1_1") (pintype "passive"))
      (node (ref "ES13") (pin "2") (pinfunction "2_2") (pintype "passive"))
      (node (ref "ES14") (pin "1") (pinfunction "1_1") (pintype "passive"))
      (node (ref "L1") (pin "1") (pinfunction "1_1") (pintype "passive"))
      (node (ref "L2") (pin "2") (pinfunction "2_2") (pintype "passive"))
    )
    (net (code "31") (name "Net-(B4-Pad2)") (class "Default")
      (node (ref "B4") (pin "2") (pinfunction "2_2") (pintype "passive"))
      (node (ref "R17") (pin "2") (pinfunction "2_2") (pintype "passive"))
    )
    (net (code "32") (name "Net-(B5-Pad2)") (class "Default")
      (node (ref "B5") (pin "2") (pinfunction "2_2") (pintype "passive"))
      (node (ref "R19") (pin "2") (pinfunction "2_2") (pintype "passive"))
    )
    (net (code "33") (name "Net-(B6-Pad2)") (class "Default")
      (node (ref "B6") (pin "2") (pinfunction "2_2") (pintype "passive"))
      (node (ref "R21") (pin "2") (pinfunction "2_2") (pintype "passive"))
    )
    (net (code "34") (name "Net-(B10-Pad1)") (class "Default")
      (node (ref "B10") (pin "1") (pinfunction "1_1") (pintype "passive"))
      (node (ref "R22") (pin "2") (pinfunction "2_2") (pintype "passive"))
      (node (ref "R27") (pin "2") (pinfunction "2_2") (pintype "passive"))
    )
    (net (code "35") (name "Net-(C7-Pad1)") (class "Default")
      (node (ref "C7") (pin "1") (pinfunction "1_1") (pintype "passive"))
      (node (ref "R22") (pin "1") (pinfunction "1_1") (pintype "passive"))
      (node (ref "R23") (pin "2") (pinfunction "2_2") (pintype "passive"))
    )
    (net (code "36") (name "Net-(ES2-Pad1)") (class "Default")
      (node (ref "ES2") (pin "1") (pinfunction "1_1") (pintype "passive"))
      (node (ref "R2") (pin "1") (pinfunction "1_1") (pintype "passive"))
      (node (ref "SW2") (pin "2") (pinfunction "2_2") (pintype "passive"))
    )
    (net (code "37") (name "Net-(J1-Pad3)") (class "Default")
      (node (ref "J1") (pin "3") (pinfunction "3_3") (pintype "passive"))
      (node (ref "R10") (pin "1") (pinfunction "1_1") (pintype "passive"))
    )
    (net (code "38") (name "Net-(LED1-A)") (class "Default")
      (node (ref "LED1") (pin "1") (pinfunction "A_1") (pintype "passive"))
      (node (ref "R3") (pin "2") (pinfunction "2_2") (pintype "passive"))
    )
    (net (code "39") (name "Net-(LED2-A)") (class "Default")
      (node (ref "LED2") (pin "1") (pinfunction "A_1") (pintype "passive"))
      (node (ref "R4") (pin "2") (pinfunction "2_2") (pintype "passive"))
    )
    (net (code "40") (name "Net-(LED3-A)") (class "Default")
      (node (ref "LED3") (pin "1") (pinfunction "A_1") (pintype "passive"))
      (node (ref "R5") (pin "2") (pinfunction "2_2") (pintype "passive"))
    )
    (net (code "41") (name "Net-(LED4-A)") (class "Default")
      (node (ref "LED4") (pin "1") (pinfunction "A_1") (pintype "passive"))
      (node (ref "R6") (pin "2") (pinfunction "2_2") (pintype "passive"))
    )
    (net (code "42") (name "Net-(LED5-A)") (class "Default")
      (node (ref "LED5") (pin "1") (pinfunction "A_1") (pintype "passive"))
      (node (ref "R7") (pin "2") (pinfunction "2_2") (pintype "passive"))
    )
    (net (code "43") (name "Net-(LED6-A)") (class "Default")
      (node (ref "LED6") (pin "1") (pinfunction "A_1") (pintype "passive"))
      (node (ref "R8") (pin "2") (pinfunction "2_2") (pintype "passive"))
    )
    (net (code "44") (name "Net-(LED7-A)") (class "Default")
      (node (ref "LED7") (pin "1") (pinfunction "A_1") (pintype "passive"))
      (node (ref "R9") (pin "2") (pinfunction "2_2") (pintype "passive"))
    )
    (net (code "45") (name "Net-(LED8-A)") (class "Default")
      (node (ref "LED8") (pin "1") (pinfunction "A_1") (pintype "passive"))
      (node (ref "R14") (pin "2") (pinfunction "2_2") (pintype "passive"))
    )
    (net (code "46") (name "Net-(LED9-A)") (class "Default")
      (node (ref "LED9") (pin "1") (pinfunction "A_1") (pintype "passive"))
      (node (ref "R15") (pin "2") (pinfunction "2_2") (pintype "passive"))
    )
    (net (code "47") (name "Net-(Q1-G)") (class "Default")
      (node (ref "Q1") (pin "1") (pinfunction "G_1") (pintype "passive"))
      (node (ref "R16") (pin "2") (pinfunction "2_2") (pintype "passive"))
      (node (ref "R20") (pin "2") (pinfunction "2_2") (pintype "passive"))
    )
    (net (code "48") (name "Net-(Q1-S)") (class "Default")
      (node (ref "B10") (pin "2") (pinfunction "2_2") (pintype "passive"))
      (node (ref "Q1") (pin "3") (pinfunction "S_3") (pintype "passive"))
    )
    (net (code "49") (name "Net-(Q2-B)") (class "Default")
      (node (ref "Q2") (pin "1") (pinfunction "B_1") (pintype "passive"))
      (node (ref "R12") (pin "2") (pinfunction "2_2") (pintype "passive"))
      (node (ref "R21") (pin "1") (pinfunction "1_1") (pintype "passive"))
      (node (ref "T9") (pin "1") (pinfunction "1_1") (pintype "passive"))
    )
    (net (code "50") (name "Net-(Q3-D)") (class "Default")
      (node (ref "J2") (pin "1") (pinfunction "1_1") (pintype "passive"))
      (node (ref "Q3") (pin "2") (pinfunction "D_2") (pintype "passive"))
    )
    (net (code "51") (name "Net-(Q3-G)") (class "Default")
      (node (ref "Q3") (pin "1") (pinfunction "G_1") (pintype "passive"))
      (node (ref "R28") (pin "2") (pinfunction "2_2") (pintype "passive"))
    )
    (net (code "52") (name "Net-(Q3-S)") (class "Default")
      (node (ref "B7") (pin "1") (pinfunction "1_1") (pintype "passive"))
      (node (ref "C10") (pin "1") (pinfunction "1_1") (pintype "passive"))
      (node (ref "C14") (pin "1") (pinfunction "1_1") (pintype "passive"))
      (node (ref "Q3") (pin "3") (pinfunction "S_3") (pintype "passive"))
      (node (ref "T6") (pin "1") (pinfunction "1_1") (pintype "passive"))
    )
    (net (code "53") (name "Net-(SD1-A)") (class "Default")
      (node (ref "L3") (pin "2") (pinfunction "2_2") (pintype "passive"))
      (node (ref "SD1") (pin "1") (pinfunction "A_1") (pintype "passive"))
      (node (ref "U3") (pin "1") (pinfunction "SW_1") (pintype "passive"))
    )
    (net (code "54") (name "Net-(U3-FB)") (class "Default")
      (node (ref "R25") (pin "1") (pinfunction "1_1") (pintype "passive"))
      (node (ref "R29") (pin "1") (pinfunction "1_1") (pintype "passive"))
      (node (ref "U3") (pin "3") (pinfunction "FB_3") (pintype "passive"))
    )
    (net (code "55") (name "unconnected-(U1-IOC{slash}RX{slash}AN11{slash}RB5-Pad12)") (class "Default")
      (node (ref "U1") (pin "12") (pinfunction "IOC/RX/AN11/RB5_12") (pintype "passive"))
    )
    (net (code "56") (name "unconnected-(U3-NC-Pad6)") (class "Default")
      (node (ref "U3") (pin "6") (pinfunction "NC_6") (pintype "passive"))
    )
  )
)
